# JRC_Board_Mini_Version1_0.net
KiCad netlist of a schematic drawn in EasyEDA
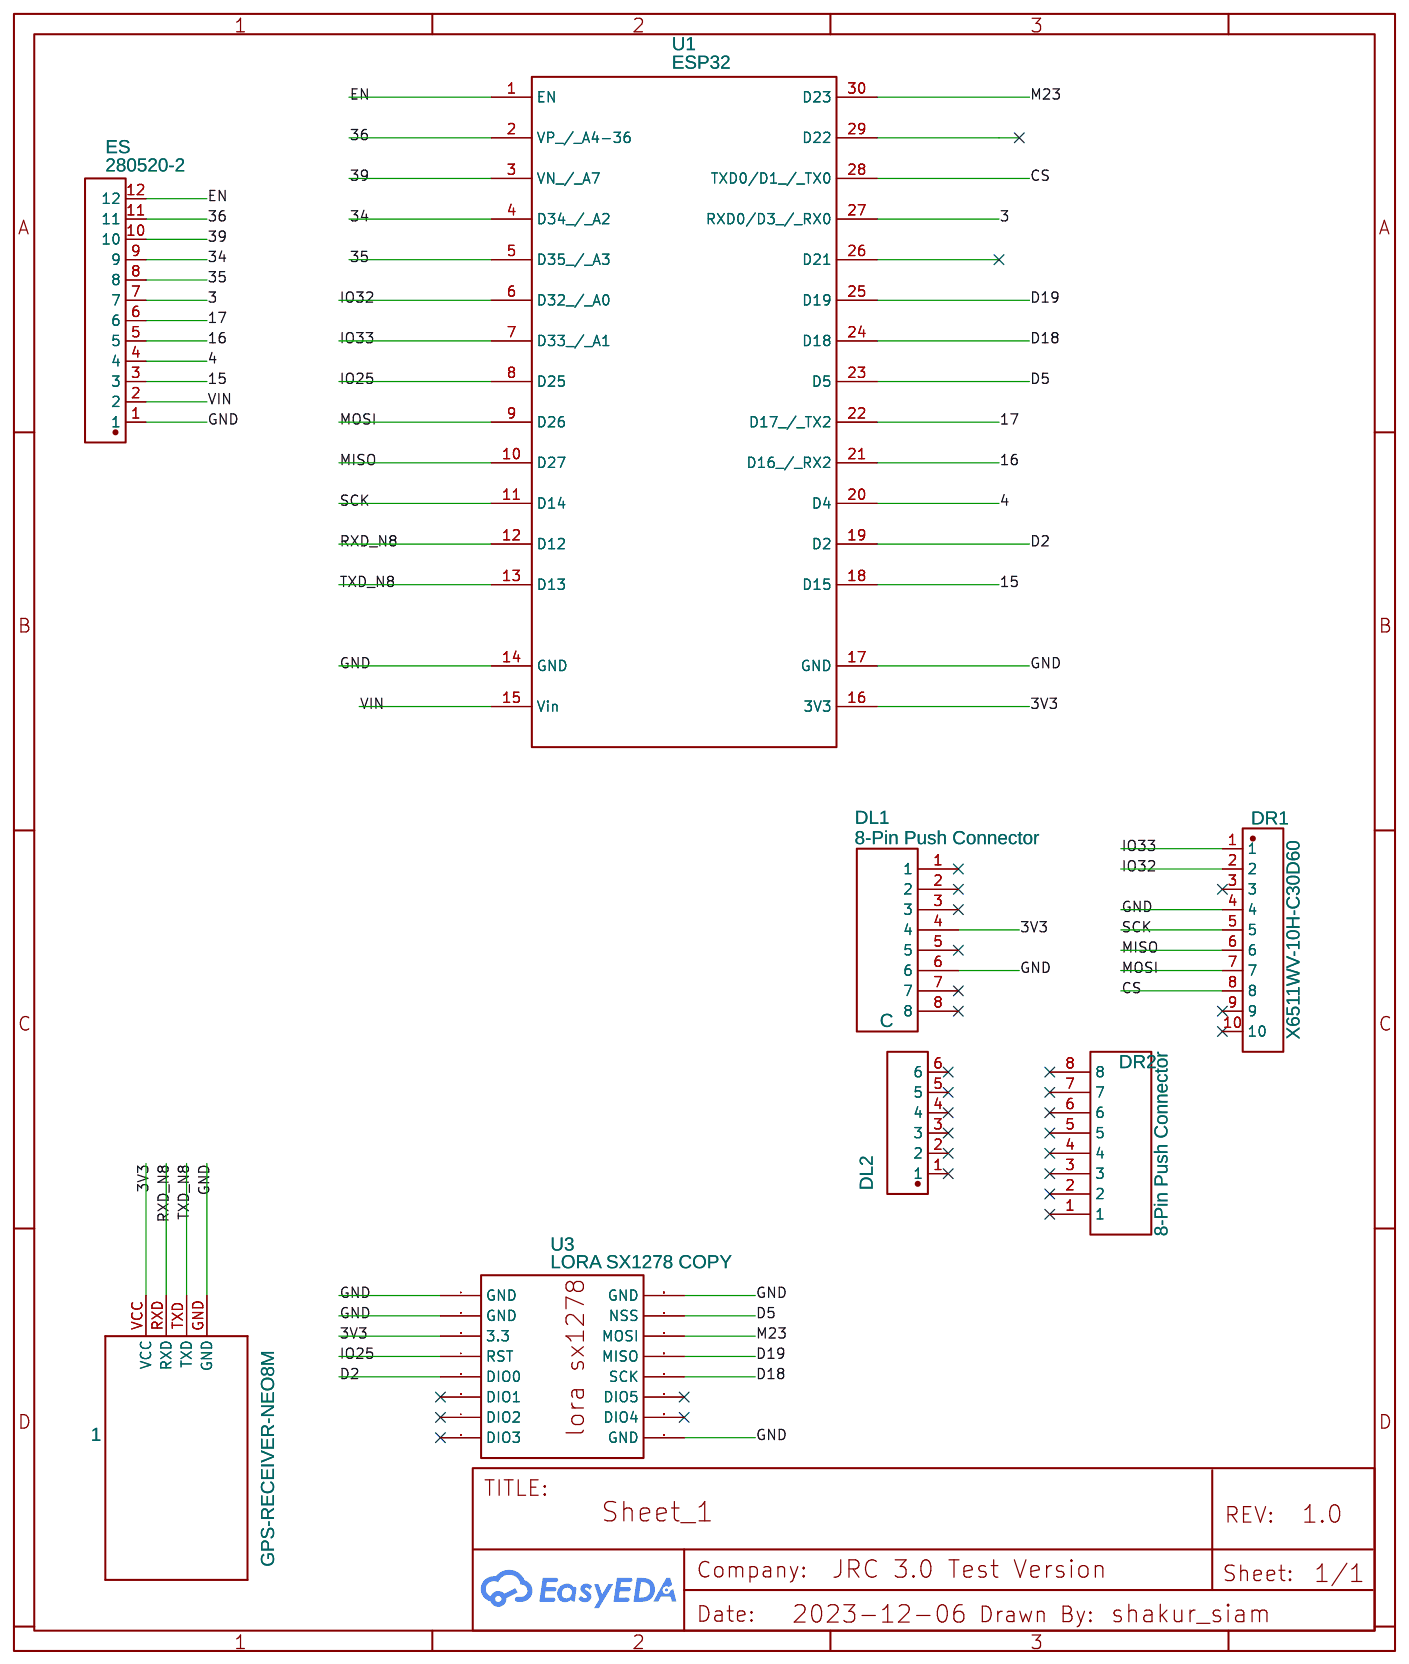
[diagram p0: schematic sheet]

(export (version "E")
  (design (tool "Eeschema 10.0.6"))
  (components
    (comp (ref "1") (value "GPS-RECEIVER-NEO8M") (libsource (lib "") (part "GPS-RECEIVER-NEO8M")))
    (comp (ref "C") (value "DL2") (libsource (lib "") (part "Connector 6-pin")))
    (comp (ref "DL1") (value "8-Pin Push Connector") (libsource (lib "") (part "8-Pin Push Connector")))
    (comp (ref "DR1")
      (value "X6511WV-10H-C30D60")
      (fields (field (name "Manufacturer") "XKB Connectivity(中国星坤)"))
      (libsource (lib "") (part "X6511WV-10H-C30D60"))
    )
    (comp (ref "DR2") (value "8-Pin Push Connector") (libsource (lib "") (part "8-Pin Push Connector_1")))
    (comp (ref "ES")
      (value "280520-2")
      (fields (field (name "Manufacturer") "TE Connectivity(泰科电子)"))
      (libsource (lib "") (part "280520-2"))
    )
    (comp (ref "U1")
      (value "ESP32")
      (fields
        (field (name "Manufacturer Part") "ESP32WROOM32")
        (field (name "Manufacturer") "Espressif Systems")
      )
      (libsource (lib "") (part "ESP32"))
    )
    (comp (ref "U3") (value "LORA SX1278 COPY") (libsource (lib "") (part "LORA SX1278 COPY")))
  )
  (nets
    (net (code "1") (name "/3") (class "Default")
      (node (ref "ES") (pin "7") (pinfunction "7_7") (pintype "unspecified"))
      (node (ref "U1") (pin "27") (pinfunction "RXD0/D3_/_RX0_27") (pintype "unspecified"))
    )
    (net (code "2") (name "/3V3") (class "Default")
      (node (ref "1") (pin "VCC") (pinfunction "VCC_VCC") (pintype "bidirectional"))
      (node (ref "DL1") (pin "4") (pinfunction "4_4") (pintype "unspecified"))
      (node (ref "U1") (pin "16") (pinfunction "3V3_16") (pintype "unspecified"))
      (node (ref "U3") (pin "3") (pinfunction "3.3_3") (pintype "unspecified"))
    )
    (net (code "3") (name "/4") (class "Default")
      (node (ref "ES") (pin "4") (pinfunction "4_4") (pintype "unspecified"))
      (node (ref "U1") (pin "20") (pinfunction "D4_20") (pintype "unspecified"))
    )
    (net (code "4") (name "/15") (class "Default")
      (node (ref "ES") (pin "3") (pinfunction "3_3") (pintype "unspecified"))
      (node (ref "U1") (pin "18") (pinfunction "D15_18") (pintype "unspecified"))
    )
    (net (code "5") (name "/16") (class "Default")
      (node (ref "ES") (pin "5") (pinfunction "5_5") (pintype "unspecified"))
      (node (ref "U1") (pin "21") (pinfunction "D16_/_RX2_21") (pintype "unspecified"))
    )
    (net (code "6") (name "/17") (class "Default")
      (node (ref "ES") (pin "6") (pinfunction "6_6") (pintype "unspecified"))
      (node (ref "U1") (pin "22") (pinfunction "D17_/_TX2_22") (pintype "unspecified"))
    )
    (net (code "7") (name "/34") (class "Default")
      (node (ref "ES") (pin "9") (pinfunction "9_9") (pintype "unspecified"))
      (node (ref "U1") (pin "4") (pinfunction "D34_/_A2_4") (pintype "unspecified"))
    )
    (net (code "8") (name "/35") (class "Default")
      (node (ref "ES") (pin "8") (pinfunction "8_8") (pintype "unspecified"))
      (node (ref "U1") (pin "5") (pinfunction "D35_/_A3_5") (pintype "unspecified"))
    )
    (net (code "9") (name "/36") (class "Default")
      (node (ref "ES") (pin "11") (pinfunction "11_11") (pintype "unspecified"))
      (node (ref "U1") (pin "2") (pinfunction "VP_/_A4-36_2") (pintype "unspecified"))
    )
    (net (code "10") (name "/39") (class "Default")
      (node (ref "ES") (pin "10") (pinfunction "10_10") (pintype "unspecified"))
      (node (ref "U1") (pin "3") (pinfunction "VN_/_A7_3") (pintype "unspecified"))
    )
    (net (code "11") (name "/CS") (class "Default")
      (node (ref "DR1") (pin "8") (pinfunction "8_8") (pintype "unspecified"))
      (node (ref "U1") (pin "28") (pinfunction "TXD0/D1_/_TX0_28") (pintype "unspecified"))
    )
    (net (code "12") (name "/D2") (class "Default")
      (node (ref "U1") (pin "19") (pinfunction "D2_19") (pintype "unspecified"))
      (node (ref "U3") (pin "5") (pinfunction "DIO0_5") (pintype "unspecified"))
    )
    (net (code "13") (name "/D5") (class "Default")
      (node (ref "U1") (pin "23") (pinfunction "D5_23") (pintype "unspecified"))
      (node (ref "U3") (pin "15") (pinfunction "NSS_15") (pintype "unspecified"))
    )
    (net (code "14") (name "/D18") (class "Default")
      (node (ref "U1") (pin "24") (pinfunction "D18_24") (pintype "unspecified"))
      (node (ref "U3") (pin "12") (pinfunction "SCK_12") (pintype "unspecified"))
    )
    (net (code "15") (name "/D19") (class "Default")
      (node (ref "U1") (pin "25") (pinfunction "D19_25") (pintype "unspecified"))
      (node (ref "U3") (pin "13") (pinfunction "MISO_13") (pintype "unspecified"))
    )
    (net (code "16") (name "/EN") (class "Default")
      (node (ref "ES") (pin "12") (pinfunction "12_12") (pintype "unspecified"))
      (node (ref "U1") (pin "1") (pinfunction "EN_1") (pintype "unspecified"))
    )
    (net (code "17") (name "/GND") (class "Default")
      (node (ref "1") (pin "GND") (pinfunction "GND_GND") (pintype "bidirectional"))
      (node (ref "DL1") (pin "6") (pinfunction "6_6") (pintype "unspecified"))
      (node (ref "DR1") (pin "4") (pinfunction "4_4") (pintype "unspecified"))
      (node (ref "ES") (pin "1") (pinfunction "1_1") (pintype "unspecified"))
      (node (ref "U1") (pin "14") (pinfunction "GND_14") (pintype "unspecified"))
      (node (ref "U1") (pin "17") (pinfunction "GND_17") (pintype "unspecified"))
      (node (ref "U3") (pin "1") (pinfunction "GND_1") (pintype "unspecified"))
      (node (ref "U3") (pin "16") (pinfunction "GND_16") (pintype "unspecified"))
      (node (ref "U3") (pin "2") (pinfunction "GND_2") (pintype "unspecified"))
      (node (ref "U3") (pin "9") (pinfunction "GND_9") (pintype "unspecified"))
    )
    (net (code "18") (name "/IO25") (class "Default")
      (node (ref "U1") (pin "8") (pinfunction "D25_8") (pintype "unspecified"))
      (node (ref "U3") (pin "4") (pinfunction "RST_4") (pintype "unspecified"))
    )
    (net (code "19") (name "/IO32") (class "Default")
      (node (ref "DR1") (pin "2") (pinfunction "2_2") (pintype "unspecified"))
      (node (ref "U1") (pin "6") (pinfunction "D32_/_A0_6") (pintype "unspecified"))
    )
    (net (code "20") (name "/IO33") (class "Default")
      (node (ref "DR1") (pin "1") (pinfunction "1_1") (pintype "unspecified"))
      (node (ref "U1") (pin "7") (pinfunction "D33_/_A1_7") (pintype "unspecified"))
    )
    (net (code "21") (name "/M23") (class "Default")
      (node (ref "U1") (pin "30") (pinfunction "D23_30") (pintype "unspecified"))
      (node (ref "U3") (pin "14") (pinfunction "MOSI_14") (pintype "unspecified"))
    )
    (net (code "22") (name "/MISO") (class "Default")
      (node (ref "DR1") (pin "6") (pinfunction "6_6") (pintype "unspecified"))
      (node (ref "U1") (pin "10") (pinfunction "D27_10") (pintype "unspecified"))
    )
    (net (code "23") (name "/MOSI") (class "Default")
      (node (ref "DR1") (pin "7") (pinfunction "7_7") (pintype "unspecified"))
      (node (ref "U1") (pin "9") (pinfunction "D26_9") (pintype "unspecified"))
    )
    (net (code "24") (name "/RXD_N8") (class "Default")
      (node (ref "1") (pin "RXD") (pinfunction "RXD_RXD") (pintype "bidirectional"))
      (node (ref "U1") (pin "12") (pinfunction "D12_12") (pintype "unspecified"))
    )
    (net (code "25") (name "/SCK") (class "Default")
      (node (ref "DR1") (pin "5") (pinfunction "5_5") (pintype "unspecified"))
      (node (ref "U1") (pin "11") (pinfunction "D14_11") (pintype "unspecified"))
    )
    (net (code "26") (name "/TXD_N8") (class "Default")
      (node (ref "1") (pin "TXD") (pinfunction "TXD_TXD") (pintype "bidirectional"))
      (node (ref "U1") (pin "13") (pinfunction "D13_13") (pintype "unspecified"))
    )
    (net (code "27") (name "/VIN") (class "Default")
      (node (ref "ES") (pin "2") (pinfunction "2_2") (pintype "unspecified"))
      (node (ref "U1") (pin "15") (pinfunction "Vin_15") (pintype "unspecified"))
    )
    (net (code "28") (name "unconnected-(C-Pad1)") (class "Default")
      (node (ref "C") (pin "1") (pinfunction "1_1") (pintype "unspecified+no_connect"))
    )
    (net (code "29") (name "unconnected-(C-Pad2)") (class "Default")
      (node (ref "C") (pin "2") (pinfunction "2_2") (pintype "unspecified+no_connect"))
    )
    (net (code "30") (name "unconnected-(C-Pad3)") (class "Default")
      (node (ref "C") (pin "3") (pinfunction "3_3") (pintype "unspecified+no_connect"))
    )
    (net (code "31") (name "unconnected-(C-Pad4)") (class "Default")
      (node (ref "C") (pin "4") (pinfunction "4_4") (pintype "unspecified+no_connect"))
    )
    (net (code "32") (name "unconnected-(C-Pad5)") (class "Default")
      (node (ref "C") (pin "5") (pinfunction "5_5") (pintype "unspecified+no_connect"))
    )
    (net (code "33") (name "unconnected-(C-Pad6)") (class "Default")
      (node (ref "C") (pin "6") (pinfunction "6_6") (pintype "unspecified+no_connect"))
    )
    (net (code "34") (name "unconnected-(DL1-Pad1)") (class "Default")
      (node (ref "DL1") (pin "1") (pinfunction "1_1") (pintype "unspecified+no_connect"))
    )
    (net (code "35") (name "unconnected-(DL1-Pad2)") (class "Default")
      (node (ref "DL1") (pin "2") (pinfunction "2_2") (pintype "unspecified+no_connect"))
    )
    (net (code "36") (name "unconnected-(DL1-Pad3)") (class "Default")
      (node (ref "DL1") (pin "3") (pinfunction "3_3") (pintype "unspecified+no_connect"))
    )
    (net (code "37") (name "unconnected-(DL1-Pad5)") (class "Default")
      (node (ref "DL1") (pin "5") (pinfunction "5_5") (pintype "unspecified+no_connect"))
    )
    (net (code "38") (name "unconnected-(DL1-Pad7)") (class "Default")
      (node (ref "DL1") (pin "7") (pinfunction "7_7") (pintype "unspecified+no_connect"))
    )
    (net (code "39") (name "unconnected-(DL1-Pad8)") (class "Default")
      (node (ref "DL1") (pin "8") (pinfunction "8_8") (pintype "unspecified+no_connect"))
    )
    (net (code "40") (name "unconnected-(DR1-Pad3)") (class "Default")
      (node (ref "DR1") (pin "3") (pinfunction "3_3") (pintype "unspecified+no_connect"))
    )
    (net (code "41") (name "unconnected-(DR1-Pad9)") (class "Default")
      (node (ref "DR1") (pin "9") (pinfunction "9_9") (pintype "unspecified+no_connect"))
    )
    (net (code "42") (name "unconnected-(DR1-Pad10)") (class "Default")
      (node (ref "DR1") (pin "10") (pinfunction "10_10") (pintype "unspecified+no_connect"))
    )
    (net (code "43") (name "unconnected-(DR2-Pad1)") (class "Default")
      (node (ref "DR2") (pin "1") (pinfunction "1_1") (pintype "unspecified+no_connect"))
    )
    (net (code "44") (name "unconnected-(DR2-Pad2)") (class "Default")
      (node (ref "DR2") (pin "2") (pinfunction "2_2") (pintype "unspecified+no_connect"))
    )
    (net (code "45") (name "unconnected-(DR2-Pad3)") (class "Default")
      (node (ref "DR2") (pin "3") (pinfunction "3_3") (pintype "unspecified+no_connect"))
    )
    (net (code "46") (name "unconnected-(DR2-Pad4)") (class "Default")
      (node (ref "DR2") (pin "4") (pinfunction "4_4") (pintype "unspecified+no_connect"))
    )
    (net (code "47") (name "unconnected-(DR2-Pad5)") (class "Default")
      (node (ref "DR2") (pin "5") (pinfunction "5_5") (pintype "unspecified+no_connect"))
    )
    (net (code "48") (name "unconnected-(DR2-Pad6)") (class "Default")
      (node (ref "DR2") (pin "6") (pinfunction "6_6") (pintype "unspecified+no_connect"))
    )
    (net (code "49") (name "unconnected-(DR2-Pad7)") (class "Default")
      (node (ref "DR2") (pin "7") (pinfunction "7_7") (pintype "unspecified+no_connect"))
    )
    (net (code "50") (name "unconnected-(DR2-Pad8)") (class "Default")
      (node (ref "DR2") (pin "8") (pinfunction "8_8") (pintype "unspecified+no_connect"))
    )
    (net (code "51") (name "unconnected-(U1-D21-Pad26)") (class "Default")
      (node (ref "U1") (pin "26") (pinfunction "D21_26") (pintype "unspecified+no_connect"))
    )
    (net (code "52") (name "unconnected-(U1-D22-Pad29)") (class "Default")
      (node (ref "U1") (pin "29") (pinfunction "D22_29") (pintype "unspecified+no_connect"))
    )
    (net (code "53") (name "unconnected-(U3-DIO1-Pad6)") (class "Default")
      (node (ref "U3") (pin "6") (pinfunction "DIO1_6") (pintype "unspecified+no_connect"))
    )
    (net (code "54") (name "unconnected-(U3-DIO2-Pad7)") (class "Default")
      (node (ref "U3") (pin "7") (pinfunction "DIO2_7") (pintype "unspecified+no_connect"))
    )
    (net (code "55") (name "unconnected-(U3-DIO3-Pad8)") (class "Default")
      (node (ref "U3") (pin "8") (pinfunction "DIO3_8") (pintype "unspecified+no_connect"))
    )
    (net (code "56") (name "unconnected-(U3-DIO4-Pad10)") (class "Default")
      (node (ref "U3") (pin "10") (pinfunction "DIO4_10") (pintype "unspecified+no_connect"))
    )
    (net (code "57") (name "unconnected-(U3-DIO5-Pad11)") (class "Default")
      (node (ref "U3") (pin "11") (pinfunction "DIO5_11") (pintype "unspecified+no_connect"))
    )
  )
)
